# 4_SensorsAndComms.net
KiCad netlist of a schematic drawn in Altium Designer
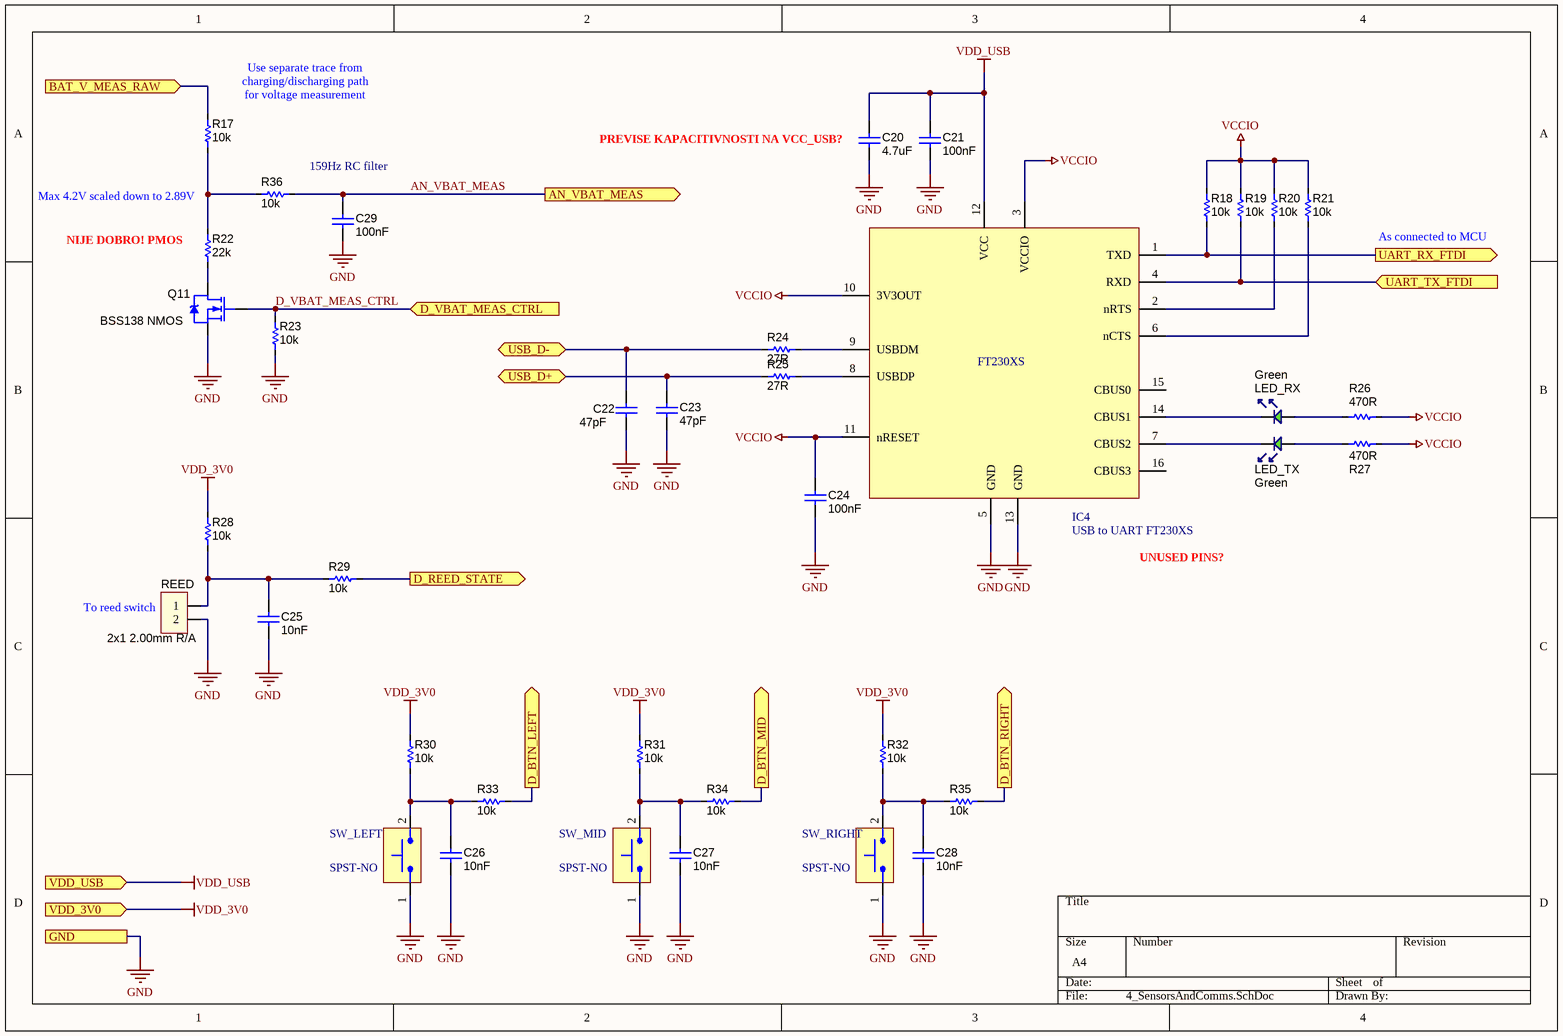
[diagram p0: 4_SensorsAndComms.SchDoc]

(export (version "E")
  (design (tool "Eeschema 10.0.6"))
  (components
    (comp (ref "C20")
      (value "4.7uF")
      (footprint "CAP_0805")
      (description "Cermacic Capacitor 0805 25V 4.7uF")
      (fields (field (name "MANUFACTURER") "n/a"))
      (libsource (lib "Diplomski") (part "CAP_4.7uF_25V_0805"))
    )
    (comp (ref "C21")
      (value "100nF")
      (footprint "CAP_0603")
      (description "Cermacic Capacitor 0603 50V 100nF")
      (fields (field (name "MANUFACTURER") "n/a"))
      (libsource (lib "Diplomski") (part "CAP_100nF_50V_0603"))
    )
    (comp (ref "C22")
      (value "47pF")
      (footprint "CAP_0603")
      (description "Ceramic Capacitor 0603 50V 47pF NPO")
      (fields (field (name "MANUFACTURER") "n/a"))
      (libsource (lib "Diplomski") (part "CAP_47pF_50V_0603"))
    )
    (comp (ref "C23")
      (value "47pF")
      (footprint "CAP_0603")
      (description "Ceramic Capacitor 0603 50V 47pF NPO")
      (fields (field (name "MANUFACTURER") "n/a"))
      (libsource (lib "Diplomski") (part "CAP_47pF_50V_0603"))
    )
    (comp (ref "C24")
      (value "100nF")
      (footprint "CAP_0603")
      (description "Cermacic Capacitor 0603 50V 100nF")
      (fields (field (name "MANUFACTURER") "n/a"))
      (libsource (lib "Diplomski") (part "CAP_100nF_50V_0603"))
    )
    (comp (ref "C25")
      (value "10nF")
      (footprint "CAP_0603")
      (description "Cermacic Capacitor 0603 16V 10nF")
      (fields (field (name "MANUFACTURER") "n/a"))
      (libsource (lib "Diplomski") (part "CAP_10nF_63V_X7R_0603"))
    )
    (comp (ref "C26")
      (value "10nF")
      (footprint "CAP_0603")
      (description "Cermacic Capacitor 0603 16V 10nF")
      (fields (field (name "MANUFACTURER") "n/a"))
      (libsource (lib "Diplomski") (part "CAP_10nF_63V_X7R_0603"))
    )
    (comp (ref "C27")
      (value "10nF")
      (footprint "CAP_0603")
      (description "Cermacic Capacitor 0603 16V 10nF")
      (fields (field (name "MANUFACTURER") "n/a"))
      (libsource (lib "Diplomski") (part "CAP_10nF_63V_X7R_0603"))
    )
    (comp (ref "C28")
      (value "10nF")
      (footprint "CAP_0603")
      (description "Cermacic Capacitor 0603 16V 10nF")
      (fields (field (name "MANUFACTURER") "n/a"))
      (libsource (lib "Diplomski") (part "CAP_10nF_63V_X7R_0603"))
    )
    (comp (ref "C29")
      (value "100nF")
      (footprint "CAP_0603")
      (description "Cermacic Capacitor 0603 50V 100nF")
      (fields (field (name "MANUFACTURER") "n/a"))
      (libsource (lib "Diplomski") (part "CAP_100nF_50V_0603"))
    )
    (comp (ref "IC4")
      (value "USB to UART FT230XS")
      (footprint "SSOP-16 (3.90mm width)")
      (description "USB 2.0 to UART interface")
      (fields (field (name "MANUFACTURER") "FTDI") (field (name "MANUFACTURER PART NUMBER") "FT230XS-R"))
      (libsource (lib "Diplomski") (part "IC_USB_SERIAL_UART_FT230XS-R_16-SSOP"))
    )
    (comp (ref "LED_RX")
      (value "Green")
      (footprint "LED_0603")
      (description "LED Diode SMD Green")
      (fields (field (name "MANUFACTURER") "n/a"))
      (libsource (lib "Diplomski") (part "LED_Green_3V_20mA_0603"))
    )
    (comp (ref "LED_TX")
      (value "Green")
      (footprint "LED_0603")
      (description "LED Diode SMD Green")
      (fields (field (name "MANUFACTURER") "n/a"))
      (libsource (lib "Diplomski") (part "LED_Green_3V_20mA_0603"))
    )
    (comp (ref "Q11")
      (value "BSS138 NMOS")
      (footprint "SOT-23-3")
      (description "MOSFET N-channel SMD BSS138 220mA 50V")
      (fields (field (name "MANUFACTURER") "ONsemi") (field (name "MANUFACTURER PART NUMBER") "BSS138"))
      (libsource (lib "Diplomski") (part "MOSFET_N_60V_220mA_BSS138_SOT-23"))
    )
    (comp (ref "R17")
      (value "10k")
      (footprint "RES_0603")
      (description "Resistor SMD 0603 10k 0.1W 1%")
      (fields (field (name "MANUFACTURER") "n/a") (field (name "TOLERANCE") "1%"))
      (libsource (lib "Diplomski") (part "RES_10k_1%_0.1W_0603"))
    )
    (comp (ref "R18")
      (value "10k")
      (footprint "RES_0603")
      (description "Resistor SMD 0603 10k 0.1W 1%")
      (fields (field (name "MANUFACTURER") "n/a") (field (name "TOLERANCE") "1%"))
      (libsource (lib "Diplomski") (part "RES_10k_1%_0.1W_0603"))
    )
    (comp (ref "R19")
      (value "10k")
      (footprint "RES_0603")
      (description "Resistor SMD 0603 10k 0.1W 1%")
      (fields (field (name "MANUFACTURER") "n/a") (field (name "TOLERANCE") "1%"))
      (libsource (lib "Diplomski") (part "RES_10k_1%_0.1W_0603"))
    )
    (comp (ref "R20")
      (value "10k")
      (footprint "RES_0603")
      (description "Resistor SMD 0603 10k 0.1W 1%")
      (fields (field (name "MANUFACTURER") "n/a") (field (name "TOLERANCE") "1%"))
      (libsource (lib "Diplomski") (part "RES_10k_1%_0.1W_0603"))
    )
    (comp (ref "R21")
      (value "10k")
      (footprint "RES_0603")
      (description "Resistor SMD 0603 10k 0.1W 1%")
      (fields (field (name "MANUFACTURER") "n/a") (field (name "TOLERANCE") "1%"))
      (libsource (lib "Diplomski") (part "RES_10k_1%_0.1W_0603"))
    )
    (comp (ref "R22")
      (value "22k")
      (footprint "RES_0603")
      (description "Resistor SMD 0603 22k 0.1W 1%")
      (fields (field (name "MANUFACTURER") "n/a") (field (name "TOLERANCE") "1%"))
      (libsource (lib "Diplomski") (part "RES_22k_1%_0.1W_0603"))
    )
    (comp (ref "R23")
      (value "10k")
      (footprint "RES_0603")
      (description "Resistor SMD 0603 10k 0.1W 1%")
      (fields (field (name "MANUFACTURER") "n/a") (field (name "TOLERANCE") "1%"))
      (libsource (lib "Diplomski") (part "RES_10k_1%_0.1W_0603"))
    )
    (comp (ref "R24")
      (value "27R")
      (footprint "RES_0603")
      (description "Resistor SMD 0603 27R 0.1W 1%")
      (fields (field (name "MANUFACTURER") "n/a") (field (name "TOLERANCE") "1%"))
      (libsource (lib "Diplomski") (part "RES_27R_1%_0.1W_0603"))
    )
    (comp (ref "R25")
      (value "27R")
      (footprint "RES_0603")
      (description "Resistor SMD 0603 27R 0.1W 1%")
      (fields (field (name "MANUFACTURER") "n/a") (field (name "TOLERANCE") "1%"))
      (libsource (lib "Diplomski") (part "RES_27R_1%_0.1W_0603"))
    )
    (comp (ref "R26")
      (value "470R")
      (footprint "RES_0603")
      (description "Resistor SMD 0603 0R 0.1W 1%")
      (fields (field (name "MANUFACTURER") "n/a") (field (name "TOLERANCE") "1%"))
      (libsource (lib "Diplomski") (part "RES_470R_1%_0.1W_0603"))
    )
    (comp (ref "R27")
      (value "470R")
      (footprint "RES_0603")
      (description "Resistor SMD 0603 0R 0.1W 1%")
      (fields (field (name "MANUFACTURER") "n/a") (field (name "TOLERANCE") "1%"))
      (libsource (lib "Diplomski") (part "RES_470R_1%_0.1W_0603"))
    )
    (comp (ref "R28")
      (value "10k")
      (footprint "RES_0603")
      (description "Resistor SMD 0603 10k 0.1W 1%")
      (fields (field (name "MANUFACTURER") "n/a") (field (name "TOLERANCE") "1%"))
      (libsource (lib "Diplomski") (part "RES_10k_1%_0.1W_0603"))
    )
    (comp (ref "R29")
      (value "10k")
      (footprint "RES_0603")
      (description "Resistor SMD 0603 10k 0.1W 1%")
      (fields (field (name "MANUFACTURER") "n/a") (field (name "TOLERANCE") "1%"))
      (libsource (lib "Diplomski") (part "RES_10k_1%_0.1W_0603"))
    )
    (comp (ref "R30")
      (value "10k")
      (footprint "RES_0603")
      (description "Resistor SMD 0603 10k 0.1W 1%")
      (fields (field (name "MANUFACTURER") "n/a") (field (name "TOLERANCE") "1%"))
      (libsource (lib "Diplomski") (part "RES_10k_1%_0.1W_0603"))
    )
    (comp (ref "R31")
      (value "10k")
      (footprint "RES_0603")
      (description "Resistor SMD 0603 10k 0.1W 1%")
      (fields (field (name "MANUFACTURER") "n/a") (field (name "TOLERANCE") "1%"))
      (libsource (lib "Diplomski") (part "RES_10k_1%_0.1W_0603"))
    )
    (comp (ref "R32")
      (value "10k")
      (footprint "RES_0603")
      (description "Resistor SMD 0603 10k 0.1W 1%")
      (fields (field (name "MANUFACTURER") "n/a") (field (name "TOLERANCE") "1%"))
      (libsource (lib "Diplomski") (part "RES_10k_1%_0.1W_0603"))
    )
    (comp (ref "R33")
      (value "10k")
      (footprint "RES_0603")
      (description "Resistor SMD 0603 10k 0.1W 1%")
      (fields (field (name "MANUFACTURER") "n/a") (field (name "TOLERANCE") "1%"))
      (libsource (lib "Diplomski") (part "RES_10k_1%_0.1W_0603"))
    )
    (comp (ref "R34")
      (value "10k")
      (footprint "RES_0603")
      (description "Resistor SMD 0603 10k 0.1W 1%")
      (fields (field (name "MANUFACTURER") "n/a") (field (name "TOLERANCE") "1%"))
      (libsource (lib "Diplomski") (part "RES_10k_1%_0.1W_0603"))
    )
    (comp (ref "R35")
      (value "10k")
      (footprint "RES_0603")
      (description "Resistor SMD 0603 10k 0.1W 1%")
      (fields (field (name "MANUFACTURER") "n/a") (field (name "TOLERANCE") "1%"))
      (libsource (lib "Diplomski") (part "RES_10k_1%_0.1W_0603"))
    )
    (comp (ref "R36")
      (value "10k")
      (footprint "RES_0603")
      (description "Resistor SMD 0603 10k 0.1W 1%")
      (fields (field (name "MANUFACTURER") "n/a") (field (name "TOLERANCE") "1%"))
      (libsource (lib "Diplomski") (part "RES_10k_1%_0.1W_0603"))
    )
    (comp (ref "REED")
      (value "2x1 2.00mm R/A")
      (footprint "JST R/A MALE 2x2.00MM")
      (description "Connector JST-PH through-hole right angle 2.0mm pitch")
      (fields
        (field (name "MANUFACTURER") "JST Sales America Inc.")
        (field (name "MANUFACTURER PART NUMBER") "S2B-PH-K-S")
      )
      (libsource (lib "Diplomski") (part "CONN_JST_TH_R/A_2x1M_2.0mm"))
    )
    (comp (ref "SW_LEFT")
      (value "SPST-NO")
      (footprint "SWITCH_TACTILE_SMD_6X3.5mm_2pin")
      (description "SMD Tactile switch 2 pin 6x3.5mm SPST-NO 5mm height")
      (fields (field (name "MANUFACTURER") "Diptronics") (field (name "MANUFACTURER PART NUMBER") "DTSM-32N"))
      (libsource (lib "Diplomski") (part "SWITCH_SMD_6X3.5mm_2pin"))
    )
    (comp (ref "SW_MID")
      (value "SPST-NO")
      (footprint "SWITCH_TACTILE_SMD_6X3.5mm_2pin")
      (description "SMD Tactile switch 2 pin 6x3.5mm SPST-NO 5mm height")
      (fields (field (name "MANUFACTURER") "Diptronics") (field (name "MANUFACTURER PART NUMBER") "DTSM-32N"))
      (libsource (lib "Diplomski") (part "SWITCH_SMD_6X3.5mm_2pin"))
    )
    (comp (ref "SW_RIGHT")
      (value "SPST-NO")
      (footprint "SWITCH_TACTILE_SMD_6X3.5mm_2pin")
      (description "SMD Tactile switch 2 pin 6x3.5mm SPST-NO 5mm height")
      (fields (field (name "MANUFACTURER") "Diptronics") (field (name "MANUFACTURER PART NUMBER") "DTSM-32N"))
      (libsource (lib "Diplomski") (part "SWITCH_SMD_6X3.5mm_2pin"))
    )
  )
  (nets
    (net (code "1") (name "/AN_VBAT_MEAS") (class "Default")
      (node (ref "C29") (pin "1") (pinfunction "1_1") (pintype "passive"))
      (node (ref "R36") (pin "1") (pinfunction "1_1") (pintype "passive"))
    )
    (net (code "2") (name "/BAT_V_MEAS_RAW") (class "Default")
      (node (ref "R17") (pin "2") (pinfunction "2_2") (pintype "passive"))
    )
    (net (code "3") (name "/D_BTN_LEFT") (class "Default")
      (node (ref "R33") (pin "1") (pinfunction "1_1") (pintype "passive"))
    )
    (net (code "4") (name "/D_BTN_MID") (class "Default")
      (node (ref "R34") (pin "1") (pinfunction "1_1") (pintype "passive"))
    )
    (net (code "5") (name "/D_BTN_RIGHT") (class "Default")
      (node (ref "R35") (pin "1") (pinfunction "1_1") (pintype "passive"))
    )
    (net (code "6") (name "/D_REED_STATE") (class "Default")
      (node (ref "R29") (pin "1") (pinfunction "1_1") (pintype "passive"))
    )
    (net (code "7") (name "/D_VBAT_MEAS_CTRL") (class "Default")
      (node (ref "Q11") (pin "1") (pinfunction "G_1") (pintype "passive"))
      (node (ref "R23") (pin "2") (pinfunction "2_2") (pintype "passive"))
    )
    (net (code "8") (name "/UART_RX_FTDI") (class "Default")
      (node (ref "IC4") (pin "1") (pinfunction "TXD_1") (pintype "passive"))
      (node (ref "R18") (pin "1") (pinfunction "1_1") (pintype "passive"))
    )
    (net (code "9") (name "/UART_TX_FTDI") (class "Default")
      (node (ref "IC4") (pin "4") (pinfunction "RXD_4") (pintype "passive"))
      (node (ref "R19") (pin "1") (pinfunction "1_1") (pintype "passive"))
    )
    (net (code "10") (name "/USB_D+") (class "Default")
      (node (ref "C23") (pin "1") (pinfunction "1_1") (pintype "passive"))
      (node (ref "R25") (pin "1") (pinfunction "1_1") (pintype "passive"))
    )
    (net (code "11") (name "/USB_D-") (class "Default")
      (node (ref "C22") (pin "1") (pinfunction "1_1") (pintype "passive"))
      (node (ref "R24") (pin "1") (pinfunction "1_1") (pintype "passive"))
    )
    (net (code "12") (name "GND") (class "Default")
      (node (ref "C20") (pin "2") (pinfunction "2_2") (pintype "passive"))
      (node (ref "C21") (pin "2") (pinfunction "2_2") (pintype "passive"))
      (node (ref "C22") (pin "2") (pinfunction "2_2") (pintype "passive"))
      (node (ref "C23") (pin "2") (pinfunction "2_2") (pintype "passive"))
      (node (ref "C24") (pin "2") (pinfunction "2_2") (pintype "passive"))
      (node (ref "C25") (pin "2") (pinfunction "2_2") (pintype "passive"))
      (node (ref "C26") (pin "2") (pinfunction "2_2") (pintype "passive"))
      (node (ref "C27") (pin "2") (pinfunction "2_2") (pintype "passive"))
      (node (ref "C28") (pin "2") (pinfunction "2_2") (pintype "passive"))
      (node (ref "C29") (pin "2") (pinfunction "2_2") (pintype "passive"))
      (node (ref "IC4") (pin "13") (pinfunction "GND_13") (pintype "passive"))
      (node (ref "IC4") (pin "5") (pinfunction "GND_5") (pintype "passive"))
      (node (ref "Q11") (pin "2") (pinfunction "S_2") (pintype "passive"))
      (node (ref "R23") (pin "1") (pinfunction "1_1") (pintype "passive"))
      (node (ref "REED") (pin "2") (pinfunction "2_2") (pintype "passive"))
      (node (ref "SW_LEFT") (pin "1") (pinfunction "1_1") (pintype "passive"))
      (node (ref "SW_MID") (pin "1") (pinfunction "1_1") (pintype "passive"))
      (node (ref "SW_RIGHT") (pin "1") (pinfunction "1_1") (pintype "passive"))
    )
    (net (code "13") (name "Net-(C25-Pad1)") (class "Default")
      (node (ref "C25") (pin "1") (pinfunction "1_1") (pintype "passive"))
      (node (ref "R28") (pin "1") (pinfunction "1_1") (pintype "passive"))
      (node (ref "R29") (pin "2") (pinfunction "2_2") (pintype "passive"))
      (node (ref "REED") (pin "1") (pinfunction "1_1") (pintype "passive"))
    )
    (net (code "14") (name "Net-(C26-Pad1)") (class "Default")
      (node (ref "C26") (pin "1") (pinfunction "1_1") (pintype "passive"))
      (node (ref "R30") (pin "1") (pinfunction "1_1") (pintype "passive"))
      (node (ref "R33") (pin "2") (pinfunction "2_2") (pintype "passive"))
      (node (ref "SW_LEFT") (pin "2") (pinfunction "2_2") (pintype "passive"))
    )
    (net (code "15") (name "Net-(C27-Pad1)") (class "Default")
      (node (ref "C27") (pin "1") (pinfunction "1_1") (pintype "passive"))
      (node (ref "R31") (pin "1") (pinfunction "1_1") (pintype "passive"))
      (node (ref "R34") (pin "2") (pinfunction "2_2") (pintype "passive"))
      (node (ref "SW_MID") (pin "2") (pinfunction "2_2") (pintype "passive"))
    )
    (net (code "16") (name "Net-(C28-Pad1)") (class "Default")
      (node (ref "C28") (pin "1") (pinfunction "1_1") (pintype "passive"))
      (node (ref "R32") (pin "1") (pinfunction "1_1") (pintype "passive"))
      (node (ref "R35") (pin "2") (pinfunction "2_2") (pintype "passive"))
      (node (ref "SW_RIGHT") (pin "2") (pinfunction "2_2") (pintype "passive"))
    )
    (net (code "17") (name "Net-(IC4-CBUS1)") (class "Default")
      (node (ref "IC4") (pin "14") (pinfunction "CBUS1_14") (pintype "passive"))
      (node (ref "LED_RX") (pin "K") (pinfunction "K_K") (pintype "passive"))
    )
    (net (code "18") (name "Net-(IC4-CBUS2)") (class "Default")
      (node (ref "IC4") (pin "7") (pinfunction "CBUS2_7") (pintype "passive"))
      (node (ref "LED_TX") (pin "K") (pinfunction "K_K") (pintype "passive"))
    )
    (net (code "19") (name "Net-(IC4-USBDM)") (class "Default")
      (node (ref "IC4") (pin "9") (pinfunction "USBDM_9") (pintype "passive"))
      (node (ref "R24") (pin "2") (pinfunction "2_2") (pintype "passive"))
    )
    (net (code "20") (name "Net-(IC4-USBDP)") (class "Default")
      (node (ref "IC4") (pin "8") (pinfunction "USBDP_8") (pintype "passive"))
      (node (ref "R25") (pin "2") (pinfunction "2_2") (pintype "passive"))
    )
    (net (code "21") (name "Net-(IC4-nCTS)") (class "Default")
      (node (ref "IC4") (pin "6") (pinfunction "nCTS_6") (pintype "passive"))
      (node (ref "R21") (pin "1") (pinfunction "1_1") (pintype "passive"))
    )
    (net (code "22") (name "Net-(IC4-nRTS)") (class "Default")
      (node (ref "IC4") (pin "2") (pinfunction "nRTS_2") (pintype "passive"))
      (node (ref "R20") (pin "1") (pinfunction "1_1") (pintype "passive"))
    )
    (net (code "23") (name "Net-(LED_RX-PadA)") (class "Default")
      (node (ref "LED_RX") (pin "A") (pinfunction "A_A") (pintype "passive"))
      (node (ref "R26") (pin "1") (pinfunction "1_1") (pintype "passive"))
    )
    (net (code "24") (name "Net-(LED_TX-PadA)") (class "Default")
      (node (ref "LED_TX") (pin "A") (pinfunction "A_A") (pintype "passive"))
      (node (ref "R27") (pin "1") (pinfunction "1_1") (pintype "passive"))
    )
    (net (code "25") (name "Net-(Q11-D)") (class "Default")
      (node (ref "Q11") (pin "3") (pinfunction "D_3") (pintype "passive"))
      (node (ref "R22") (pin "1") (pinfunction "1_1") (pintype "passive"))
    )
    (net (code "26") (name "Net-(R17-Pad1)") (class "Default")
      (node (ref "R17") (pin "1") (pinfunction "1_1") (pintype "passive"))
      (node (ref "R22") (pin "2") (pinfunction "2_2") (pintype "passive"))
      (node (ref "R36") (pin "2") (pinfunction "2_2") (pintype "passive"))
    )
    (net (code "27") (name "VCCIO") (class "Default")
      (node (ref "C24") (pin "1") (pinfunction "1_1") (pintype "passive"))
      (node (ref "IC4") (pin "10") (pinfunction "3V3OUT_10") (pintype "passive"))
      (node (ref "IC4") (pin "11") (pinfunction "nRESET_11") (pintype "passive"))
      (node (ref "IC4") (pin "3") (pinfunction "VCCIO_3") (pintype "passive"))
      (node (ref "R18") (pin "2") (pinfunction "2_2") (pintype "passive"))
      (node (ref "R19") (pin "2") (pinfunction "2_2") (pintype "passive"))
      (node (ref "R20") (pin "2") (pinfunction "2_2") (pintype "passive"))
      (node (ref "R21") (pin "2") (pinfunction "2_2") (pintype "passive"))
      (node (ref "R26") (pin "2") (pinfunction "2_2") (pintype "passive"))
      (node (ref "R27") (pin "2") (pinfunction "2_2") (pintype "passive"))
    )
    (net (code "28") (name "VDD_3V0") (class "Default")
      (node (ref "R28") (pin "2") (pinfunction "2_2") (pintype "passive"))
      (node (ref "R30") (pin "2") (pinfunction "2_2") (pintype "passive"))
      (node (ref "R31") (pin "2") (pinfunction "2_2") (pintype "passive"))
      (node (ref "R32") (pin "2") (pinfunction "2_2") (pintype "passive"))
    )
    (net (code "29") (name "VDD_USB") (class "Default")
      (node (ref "C20") (pin "1") (pinfunction "1_1") (pintype "passive"))
      (node (ref "C21") (pin "1") (pinfunction "1_1") (pintype "passive"))
      (node (ref "IC4") (pin "12") (pinfunction "VCC_12") (pintype "passive"))
    )
    (net (code "30") (name "unconnected-(IC4-CBUS0-Pad15)") (class "Default")
      (node (ref "IC4") (pin "15") (pinfunction "CBUS0_15") (pintype "passive"))
    )
    (net (code "31") (name "unconnected-(IC4-CBUS3-Pad16)") (class "Default")
      (node (ref "IC4") (pin "16") (pinfunction "CBUS3_16") (pintype "passive"))
    )
  )
)
